# 8__Peripherals.net
KiCad netlist of a schematic drawn in Altium Designer
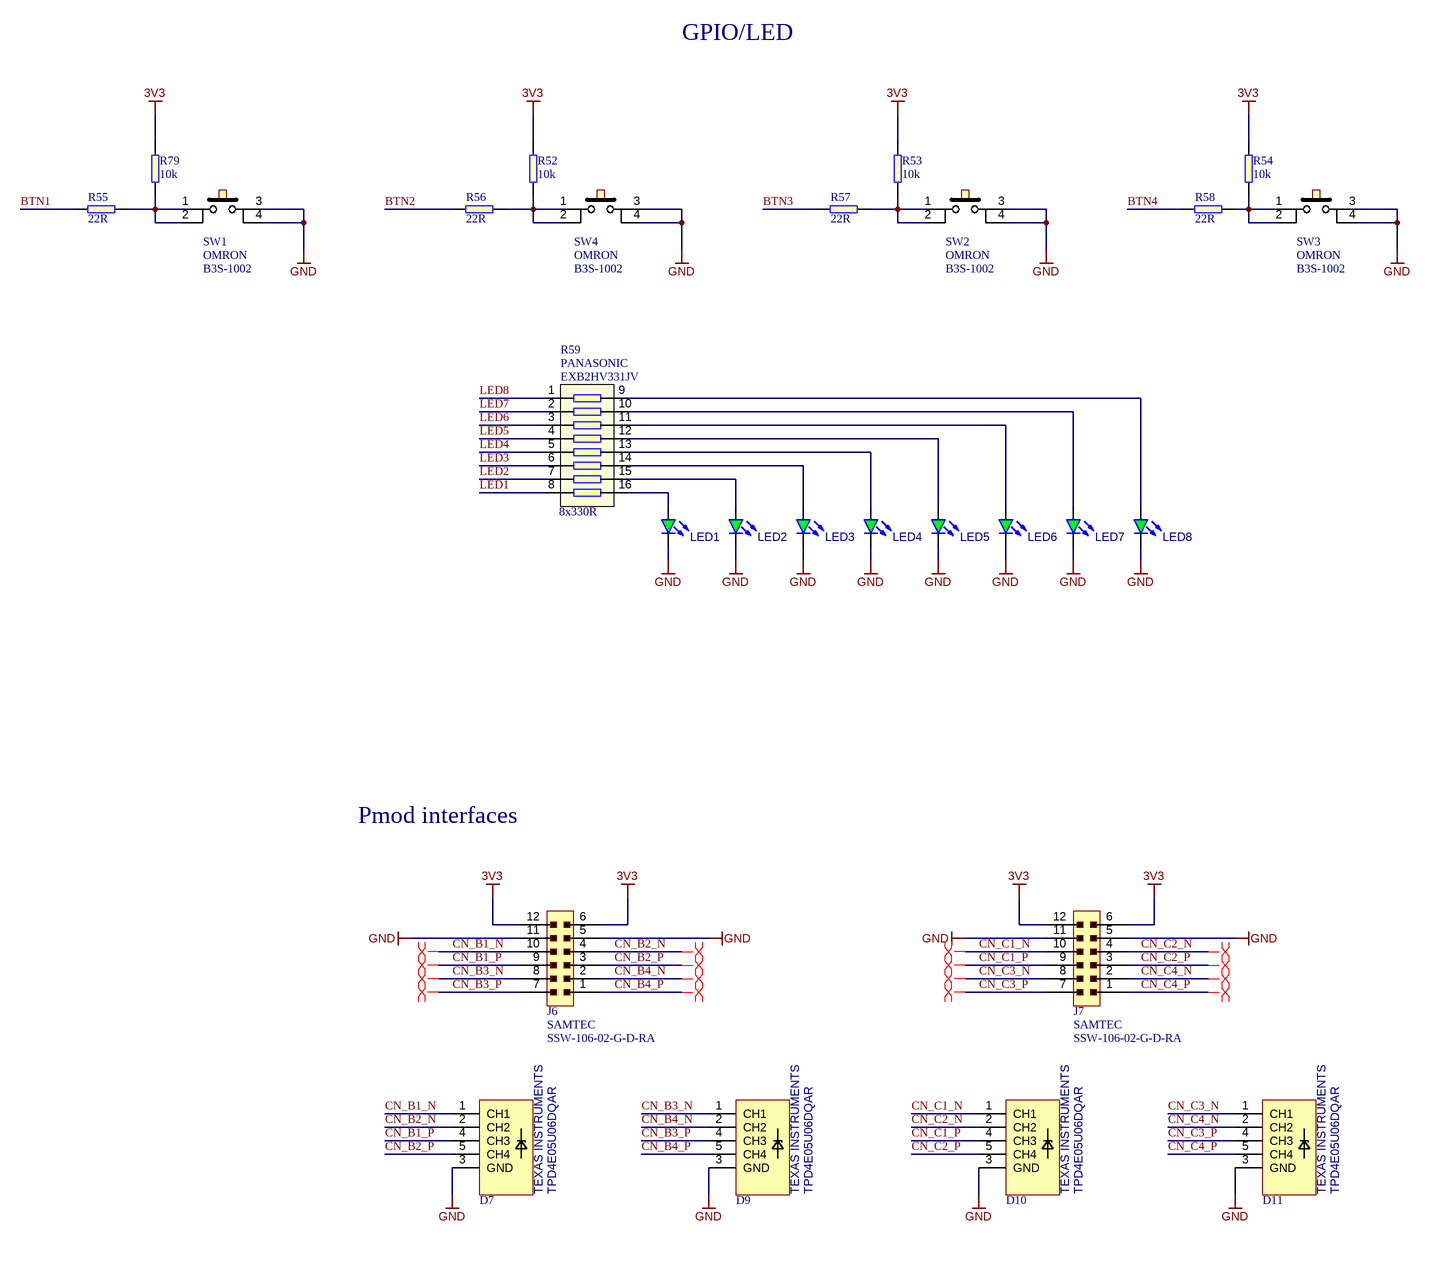
[diagram p0: [8]_Peripherals.SchDoc]

(export (version "E")
  (design (tool "Eeschema 10.0.6"))
  (components
    (comp (ref "D7")
      (value "TPD4E05U06")
      (footprint "TPD4E05U06_PASS")
      (description "ESD Suppressors 4-CH")
      (fields
        (field (name "PART NUMBER") "TPD4E05U06_PASS")
        (field (name "MANUFACTURER") "TEXAS INSTRUMENTS")
        (field (name "PART SYMBOL") "TPD4E05U06DQAR")
      )
      (libsource (lib "Zynq-Video-Board-Rev-1.2") (part "TPD4E05U06"))
    )
    (comp (ref "D9")
      (value "TPD4E05U06")
      (footprint "TPD4E05U06_PASS")
      (description "ESD Suppressors 4-CH")
      (fields
        (field (name "PART NUMBER") "TPD4E05U06_PASS")
        (field (name "MANUFACTURER") "TEXAS INSTRUMENTS")
        (field (name "PART SYMBOL") "TPD4E05U06DQAR")
      )
      (libsource (lib "Zynq-Video-Board-Rev-1.2") (part "TPD4E05U06"))
    )
    (comp (ref "D10")
      (value "TPD4E05U06")
      (footprint "TPD4E05U06_PASS")
      (description "ESD Suppressors 4-CH")
      (fields
        (field (name "PART NUMBER") "TPD4E05U06_PASS")
        (field (name "MANUFACTURER") "TEXAS INSTRUMENTS")
        (field (name "PART SYMBOL") "TPD4E05U06DQAR")
      )
      (libsource (lib "Zynq-Video-Board-Rev-1.2") (part "TPD4E05U06"))
    )
    (comp (ref "D11")
      (value "TPD4E05U06")
      (footprint "TPD4E05U06_PASS")
      (description "ESD Suppressors 4-CH")
      (fields
        (field (name "PART NUMBER") "TPD4E05U06_PASS")
        (field (name "MANUFACTURER") "TEXAS INSTRUMENTS")
        (field (name "PART SYMBOL") "TPD4E05U06DQAR")
      )
      (libsource (lib "Zynq-Video-Board-Rev-1.2") (part "TPD4E05U06"))
    )
    (comp (ref "J6")
      (value "SSW-106-02-G-D-RA")
      (footprint "SSW-106-02-G-D-RA")
      (description "Board-To-Board Connector, Right Angle, 2.54 mm, 12 Contacts, Receptacle, SSW Series, Through Hole")
      (fields (field (name "PART NUMBER") "SSW-106-02-G-D-RA") (field (name "MANUFACTURER") "SAMTEC"))
      (libsource (lib "Zynq-Video-Board-Rev-1.2") (part "SSW-106-02-G-D-RA"))
    )
    (comp (ref "J7")
      (value "SSW-106-02-G-D-RA")
      (footprint "SSW-106-02-G-D-RA")
      (description "Board-To-Board Connector, Right Angle, 2.54 mm, 12 Contacts, Receptacle, SSW Series, Through Hole")
      (fields (field (name "PART NUMBER") "SSW-106-02-G-D-RA") (field (name "MANUFACTURER") "SAMTEC"))
      (libsource (lib "Zynq-Video-Board-Rev-1.2") (part "SSW-106-02-G-D-RA"))
    )
    (comp (ref "LED1")
      (value "KPT-1608SGC")
      (footprint "LED0603")
      (description "LED Green 0603 case")
      (fields (field (name "PART NUMBER") "LED_G") (field (name "MANUFACTURER") "KINGBRIGHT"))
      (libsource (lib "Zynq-Video-Board-Rev-1.2") (part "LED"))
    )
    (comp (ref "LED2")
      (value "KPT-1608SGC")
      (footprint "LED0603")
      (description "LED Green 0603 case")
      (fields (field (name "PART NUMBER") "LED_G") (field (name "MANUFACTURER") "KINGBRIGHT"))
      (libsource (lib "Zynq-Video-Board-Rev-1.2") (part "LED"))
    )
    (comp (ref "LED3")
      (value "KPT-1608SGC")
      (footprint "LED0603")
      (description "LED Green 0603 case")
      (fields (field (name "PART NUMBER") "LED_G") (field (name "MANUFACTURER") "KINGBRIGHT"))
      (libsource (lib "Zynq-Video-Board-Rev-1.2") (part "LED"))
    )
    (comp (ref "LED4")
      (value "KPT-1608SGC")
      (footprint "LED0603")
      (description "LED Green 0603 case")
      (fields (field (name "PART NUMBER") "LED_G") (field (name "MANUFACTURER") "KINGBRIGHT"))
      (libsource (lib "Zynq-Video-Board-Rev-1.2") (part "LED"))
    )
    (comp (ref "LED5")
      (value "KPT-1608SGC")
      (footprint "LED0603")
      (description "LED Green 0603 case")
      (fields (field (name "PART NUMBER") "LED_G") (field (name "MANUFACTURER") "KINGBRIGHT"))
      (libsource (lib "Zynq-Video-Board-Rev-1.2") (part "LED"))
    )
    (comp (ref "LED6")
      (value "KPT-1608SGC")
      (footprint "LED0603")
      (description "LED Green 0603 case")
      (fields (field (name "PART NUMBER") "LED_G") (field (name "MANUFACTURER") "KINGBRIGHT"))
      (libsource (lib "Zynq-Video-Board-Rev-1.2") (part "LED"))
    )
    (comp (ref "LED7")
      (value "KPT-1608SGC")
      (footprint "LED0603")
      (description "LED Green 0603 case")
      (fields (field (name "PART NUMBER") "LED_G") (field (name "MANUFACTURER") "KINGBRIGHT"))
      (libsource (lib "Zynq-Video-Board-Rev-1.2") (part "LED"))
    )
    (comp (ref "LED8")
      (value "KPT-1608SGC")
      (footprint "LED0603")
      (description "LED Green 0603 case")
      (fields (field (name "PART NUMBER") "LED_G") (field (name "MANUFACTURER") "KINGBRIGHT"))
      (libsource (lib "Zynq-Video-Board-Rev-1.2") (part "LED"))
    )
    (comp (ref "R52")
      (value "10k")
      (footprint "0402")
      (description "SMT Resistor 10k 0402")
      (fields (field (name "PART NUMBER") "R_10k_0402") (field (name "TOLERANCE") "1%"))
      (libsource (lib "Zynq-Video-Board-Rev-1.2") (part "R_10k_0402"))
    )
    (comp (ref "R53")
      (value "10k")
      (footprint "0402")
      (description "SMT Resistor 10k 0402")
      (fields (field (name "PART NUMBER") "R_10k_0402") (field (name "TOLERANCE") "1%"))
      (libsource (lib "Zynq-Video-Board-Rev-1.2") (part "R_10k_0402"))
    )
    (comp (ref "R54")
      (value "10k")
      (footprint "0402")
      (description "SMT Resistor 10k 0402")
      (fields (field (name "PART NUMBER") "R_10k_0402") (field (name "TOLERANCE") "1%"))
      (libsource (lib "Zynq-Video-Board-Rev-1.2") (part "R_10k_0402"))
    )
    (comp (ref "R55")
      (value "22R")
      (footprint "0402")
      (description "SMT Resistor 22R 0402")
      (fields (field (name "PART NUMBER") "R_22R_0402") (field (name "TOLERANCE") "1%"))
      (libsource (lib "Zynq-Video-Board-Rev-1.2") (part "R_22R_0402"))
    )
    (comp (ref "R56")
      (value "22R")
      (footprint "0402")
      (description "SMT Resistor 22R 0402")
      (fields (field (name "PART NUMBER") "R_22R_0402") (field (name "TOLERANCE") "1%"))
      (libsource (lib "Zynq-Video-Board-Rev-1.2") (part "R_22R_0402"))
    )
    (comp (ref "R57")
      (value "22R")
      (footprint "0402")
      (description "SMT Resistor 22R 0402")
      (fields (field (name "PART NUMBER") "R_22R_0402") (field (name "TOLERANCE") "1%"))
      (libsource (lib "Zynq-Video-Board-Rev-1.2") (part "R_22R_0402"))
    )
    (comp (ref "R58")
      (value "22R")
      (footprint "0402")
      (description "SMT Resistor 22R 0402")
      (fields (field (name "PART NUMBER") "R_22R_0402") (field (name "TOLERANCE") "1%"))
      (libsource (lib "Zynq-Video-Board-Rev-1.2") (part "R_22R_0402"))
    )
    (comp (ref "R59")
      (value "8x330R")
      (footprint "R_ARRAY_0402")
      (description "SMD Resistors Array 0402")
      (fields
        (field (name "PART NUMBER") "Resistor Array_8x330R_0402")
        (field (name "TOLERANCE") "5%")
        (field (name "MANUFACTURER") "PANASONIC")
        (field (name "PART SYMBOL") "EXB2HV331JV")
      )
      (libsource (lib "Zynq-Video-Board-Rev-1.2") (part "R_ARRAY"))
    )
    (comp (ref "R79")
      (value "10k")
      (footprint "0402")
      (description "SMT Resistor 10k 0402")
      (fields (field (name "PART NUMBER") "R_10k_0402") (field (name "TOLERANCE") "1%"))
      (libsource (lib "Zynq-Video-Board-Rev-1.2") (part "R_10k_0402"))
    )
    (comp (ref "SW1")
      (value "B3S-1002")
      (footprint "B3S-100X")
      (description "Tactile switch")
      (fields (field (name "MANUFACTURER") "OMRON"))
      (libsource (lib "Zynq-Video-Board-Rev-1.2") (part "TACTILE_SWITCH"))
    )
    (comp (ref "SW2")
      (value "B3S-1002")
      (footprint "B3S-100X")
      (description "Tactile switch")
      (fields (field (name "MANUFACTURER") "OMRON"))
      (libsource (lib "Zynq-Video-Board-Rev-1.2") (part "TACTILE_SWITCH"))
    )
    (comp (ref "SW3")
      (value "B3S-100X")
      (footprint "B3S-100X")
      (description "Tactile switch")
      (fields
        (field (name "PART NUMBER") "B3S-1002")
        (field (name "MANUFACTURER") "OMRON")
        (field (name "PART SYMBOL") "B3S-1002")
      )
      (libsource (lib "Zynq-Video-Board-Rev-1.2") (part "TACTILE_SWITCH"))
    )
    (comp (ref "SW4")
      (value "B3S-100X")
      (footprint "B3S-100X")
      (description "Tactile switch")
      (fields
        (field (name "PART NUMBER") "B3S-1002")
        (field (name "MANUFACTURER") "OMRON")
        (field (name "PART SYMBOL") "B3S-1002")
      )
      (libsource (lib "Zynq-Video-Board-Rev-1.2") (part "TACTILE_SWITCH"))
    )
  )
  (nets
    (net (code "1") (name "/BTN1") (class "Default") (node (ref "R55") (pin "1") (pintype "passive")))
    (net (code "2") (name "/BTN2") (class "Default") (node (ref "R56") (pin "1") (pintype "passive")))
    (net (code "3") (name "/BTN3") (class "Default") (node (ref "R57") (pin "1") (pintype "passive")))
    (net (code "4") (name "/BTN4") (class "Default") (node (ref "R58") (pin "1") (pintype "passive")))
    (net (code "5") (name "/CN_B1_N") (class "Default")
      (node (ref "D7") (pin "1") (pinfunction "CH1_1") (pintype "passive"))
      (node (ref "J6") (pin "10") (pinfunction "10_10") (pintype "passive"))
    )
    (net (code "6") (name "/CN_B1_P") (class "Default")
      (node (ref "D7") (pin "4") (pinfunction "CH3_4") (pintype "passive"))
      (node (ref "J6") (pin "9") (pinfunction "9_9") (pintype "passive"))
    )
    (net (code "7") (name "/CN_B2_N") (class "Default")
      (node (ref "D7") (pin "2") (pinfunction "CH2_2") (pintype "passive"))
      (node (ref "J6") (pin "4") (pinfunction "4_4") (pintype "passive"))
    )
    (net (code "8") (name "/CN_B2_P") (class "Default")
      (node (ref "D7") (pin "5") (pinfunction "CH4_5") (pintype "passive"))
      (node (ref "J6") (pin "3") (pinfunction "3_3") (pintype "passive"))
    )
    (net (code "9") (name "/CN_B3_N") (class "Default")
      (node (ref "D9") (pin "1") (pinfunction "CH1_1") (pintype "passive"))
      (node (ref "J6") (pin "8") (pinfunction "8_8") (pintype "passive"))
    )
    (net (code "10") (name "/CN_B3_P") (class "Default")
      (node (ref "D9") (pin "4") (pinfunction "CH3_4") (pintype "passive"))
      (node (ref "J6") (pin "7") (pinfunction "7_7") (pintype "passive"))
    )
    (net (code "11") (name "/CN_B4_N") (class "Default")
      (node (ref "D9") (pin "2") (pinfunction "CH2_2") (pintype "passive"))
      (node (ref "J6") (pin "2") (pinfunction "2_2") (pintype "passive"))
    )
    (net (code "12") (name "/CN_B4_P") (class "Default")
      (node (ref "D9") (pin "5") (pinfunction "CH4_5") (pintype "passive"))
      (node (ref "J6") (pin "1") (pinfunction "1_1") (pintype "passive"))
    )
    (net (code "13") (name "/CN_C1_N") (class "Default")
      (node (ref "D10") (pin "1") (pinfunction "CH1_1") (pintype "passive"))
      (node (ref "J7") (pin "10") (pinfunction "10_10") (pintype "passive"))
    )
    (net (code "14") (name "/CN_C1_P") (class "Default")
      (node (ref "D10") (pin "4") (pinfunction "CH3_4") (pintype "passive"))
      (node (ref "J7") (pin "9") (pinfunction "9_9") (pintype "passive"))
    )
    (net (code "15") (name "/CN_C2_N") (class "Default")
      (node (ref "D10") (pin "2") (pinfunction "CH2_2") (pintype "passive"))
      (node (ref "J7") (pin "4") (pinfunction "4_4") (pintype "passive"))
    )
    (net (code "16") (name "/CN_C2_P") (class "Default")
      (node (ref "D10") (pin "5") (pinfunction "CH4_5") (pintype "passive"))
      (node (ref "J7") (pin "3") (pinfunction "3_3") (pintype "passive"))
    )
    (net (code "17") (name "/CN_C3_N") (class "Default")
      (node (ref "D11") (pin "1") (pinfunction "CH1_1") (pintype "passive"))
      (node (ref "J7") (pin "8") (pinfunction "8_8") (pintype "passive"))
    )
    (net (code "18") (name "/CN_C3_P") (class "Default")
      (node (ref "D11") (pin "4") (pinfunction "CH3_4") (pintype "passive"))
      (node (ref "J7") (pin "7") (pinfunction "7_7") (pintype "passive"))
    )
    (net (code "19") (name "/CN_C4_N") (class "Default")
      (node (ref "D11") (pin "2") (pinfunction "CH2_2") (pintype "passive"))
      (node (ref "J7") (pin "2") (pinfunction "2_2") (pintype "passive"))
    )
    (net (code "20") (name "/CN_C4_P") (class "Default")
      (node (ref "D11") (pin "5") (pinfunction "CH4_5") (pintype "passive"))
      (node (ref "J7") (pin "1") (pinfunction "1_1") (pintype "passive"))
    )
    (net (code "21") (name "/LED1") (class "Default")
      (node (ref "R59") (pin "8") (pinfunction "8_8") (pintype "passive"))
    )
    (net (code "22") (name "/LED2") (class "Default")
      (node (ref "R59") (pin "7") (pinfunction "7_7") (pintype "passive"))
    )
    (net (code "23") (name "/LED3") (class "Default")
      (node (ref "R59") (pin "6") (pinfunction "6_6") (pintype "passive"))
    )
    (net (code "24") (name "/LED4") (class "Default")
      (node (ref "R59") (pin "5") (pinfunction "5_5") (pintype "passive"))
    )
    (net (code "25") (name "/LED5") (class "Default")
      (node (ref "R59") (pin "4") (pinfunction "4_4") (pintype "passive"))
    )
    (net (code "26") (name "/LED6") (class "Default")
      (node (ref "R59") (pin "3") (pinfunction "3_3") (pintype "passive"))
    )
    (net (code "27") (name "/LED7") (class "Default")
      (node (ref "R59") (pin "2") (pinfunction "2_2") (pintype "passive"))
    )
    (net (code "28") (name "/LED8") (class "Default")
      (node (ref "R59") (pin "1") (pinfunction "1_1") (pintype "passive"))
    )
    (net (code "29") (name "3V3") (class "Default")
      (node (ref "J6") (pin "12") (pinfunction "12_12") (pintype "passive"))
      (node (ref "J6") (pin "6") (pinfunction "6_6") (pintype "passive"))
      (node (ref "J7") (pin "12") (pinfunction "12_12") (pintype "passive"))
      (node (ref "J7") (pin "6") (pinfunction "6_6") (pintype "passive"))
      (node (ref "R52") (pin "2") (pintype "passive"))
      (node (ref "R53") (pin "2") (pintype "passive"))
      (node (ref "R54") (pin "2") (pintype "passive"))
      (node (ref "R79") (pin "2") (pintype "passive"))
    )
    (net (code "30") (name "GND") (class "Default")
      (node (ref "D10") (pin "3") (pinfunction "GND_3") (pintype "passive"))
      (node (ref "D11") (pin "3") (pinfunction "GND_3") (pintype "passive"))
      (node (ref "D7") (pin "3") (pinfunction "GND_3") (pintype "passive"))
      (node (ref "D9") (pin "3") (pinfunction "GND_3") (pintype "passive"))
      (node (ref "J6") (pin "11") (pinfunction "11_11") (pintype "passive"))
      (node (ref "J6") (pin "5") (pinfunction "5_5") (pintype "passive"))
      (node (ref "J7") (pin "11") (pinfunction "11_11") (pintype "passive"))
      (node (ref "J7") (pin "5") (pinfunction "5_5") (pintype "passive"))
      (node (ref "LED1") (pin "K") (pinfunction "K_K") (pintype "passive"))
      (node (ref "LED2") (pin "K") (pinfunction "K_K") (pintype "passive"))
      (node (ref "LED3") (pin "K") (pinfunction "K_K") (pintype "passive"))
      (node (ref "LED4") (pin "K") (pinfunction "K_K") (pintype "passive"))
      (node (ref "LED5") (pin "K") (pinfunction "K_K") (pintype "passive"))
      (node (ref "LED6") (pin "K") (pinfunction "K_K") (pintype "passive"))
      (node (ref "LED7") (pin "K") (pinfunction "K_K") (pintype "passive"))
      (node (ref "LED8") (pin "K") (pinfunction "K_K") (pintype "passive"))
      (node (ref "SW1") (pin "3") (pinfunction "3_3") (pintype "passive"))
      (node (ref "SW1") (pin "4") (pinfunction "4_4") (pintype "passive"))
      (node (ref "SW2") (pin "3") (pinfunction "3_3") (pintype "passive"))
      (node (ref "SW2") (pin "4") (pinfunction "4_4") (pintype "passive"))
      (node (ref "SW3") (pin "3") (pinfunction "3_3") (pintype "passive"))
      (node (ref "SW3") (pin "4") (pinfunction "4_4") (pintype "passive"))
      (node (ref "SW4") (pin "3") (pinfunction "3_3") (pintype "passive"))
      (node (ref "SW4") (pin "4") (pinfunction "4_4") (pintype "passive"))
    )
    (net (code "31") (name "Net-(LED1-PadA)") (class "Default")
      (node (ref "LED1") (pin "A") (pinfunction "A_A") (pintype "passive"))
      (node (ref "R59") (pin "16") (pinfunction "16_16") (pintype "passive"))
    )
    (net (code "32") (name "Net-(LED2-PadA)") (class "Default")
      (node (ref "LED2") (pin "A") (pinfunction "A_A") (pintype "passive"))
      (node (ref "R59") (pin "15") (pinfunction "15_15") (pintype "passive"))
    )
    (net (code "33") (name "Net-(LED3-PadA)") (class "Default")
      (node (ref "LED3") (pin "A") (pinfunction "A_A") (pintype "passive"))
      (node (ref "R59") (pin "14") (pinfunction "14_14") (pintype "passive"))
    )
    (net (code "34") (name "Net-(LED4-PadA)") (class "Default")
      (node (ref "LED4") (pin "A") (pinfunction "A_A") (pintype "passive"))
      (node (ref "R59") (pin "13") (pinfunction "13_13") (pintype "passive"))
    )
    (net (code "35") (name "Net-(LED5-PadA)") (class "Default")
      (node (ref "LED5") (pin "A") (pinfunction "A_A") (pintype "passive"))
      (node (ref "R59") (pin "12") (pinfunction "12_12") (pintype "passive"))
    )
    (net (code "36") (name "Net-(LED6-PadA)") (class "Default")
      (node (ref "LED6") (pin "A") (pinfunction "A_A") (pintype "passive"))
      (node (ref "R59") (pin "11") (pinfunction "11_11") (pintype "passive"))
    )
    (net (code "37") (name "Net-(LED7-PadA)") (class "Default")
      (node (ref "LED7") (pin "A") (pinfunction "A_A") (pintype "passive"))
      (node (ref "R59") (pin "10") (pinfunction "10_10") (pintype "passive"))
    )
    (net (code "38") (name "Net-(LED8-PadA)") (class "Default")
      (node (ref "LED8") (pin "A") (pinfunction "A_A") (pintype "passive"))
      (node (ref "R59") (pin "9") (pinfunction "9_9") (pintype "passive"))
    )
    (net (code "39") (name "Net-(R52-Pad1)") (class "Default")
      (node (ref "R52") (pin "1") (pintype "passive"))
      (node (ref "R56") (pin "2") (pintype "passive"))
      (node (ref "SW4") (pin "1") (pinfunction "1_1") (pintype "passive"))
      (node (ref "SW4") (pin "2") (pinfunction "2_2") (pintype "passive"))
    )
    (net (code "40") (name "Net-(R53-Pad1)") (class "Default")
      (node (ref "R53") (pin "1") (pintype "passive"))
      (node (ref "R57") (pin "2") (pintype "passive"))
      (node (ref "SW2") (pin "1") (pinfunction "1_1") (pintype "passive"))
      (node (ref "SW2") (pin "2") (pinfunction "2_2") (pintype "passive"))
    )
    (net (code "41") (name "Net-(R54-Pad1)") (class "Default")
      (node (ref "R54") (pin "1") (pintype "passive"))
      (node (ref "R58") (pin "2") (pintype "passive"))
      (node (ref "SW3") (pin "1") (pinfunction "1_1") (pintype "passive"))
      (node (ref "SW3") (pin "2") (pinfunction "2_2") (pintype "passive"))
    )
    (net (code "42") (name "Net-(R55-Pad2)") (class "Default")
      (node (ref "R55") (pin "2") (pintype "passive"))
      (node (ref "R79") (pin "1") (pintype "passive"))
      (node (ref "SW1") (pin "1") (pinfunction "1_1") (pintype "passive"))
      (node (ref "SW1") (pin "2") (pinfunction "2_2") (pintype "passive"))
    )
  )
)
